# recco-rig.net
KiCad netlist of a schematic drawn in EAGLE
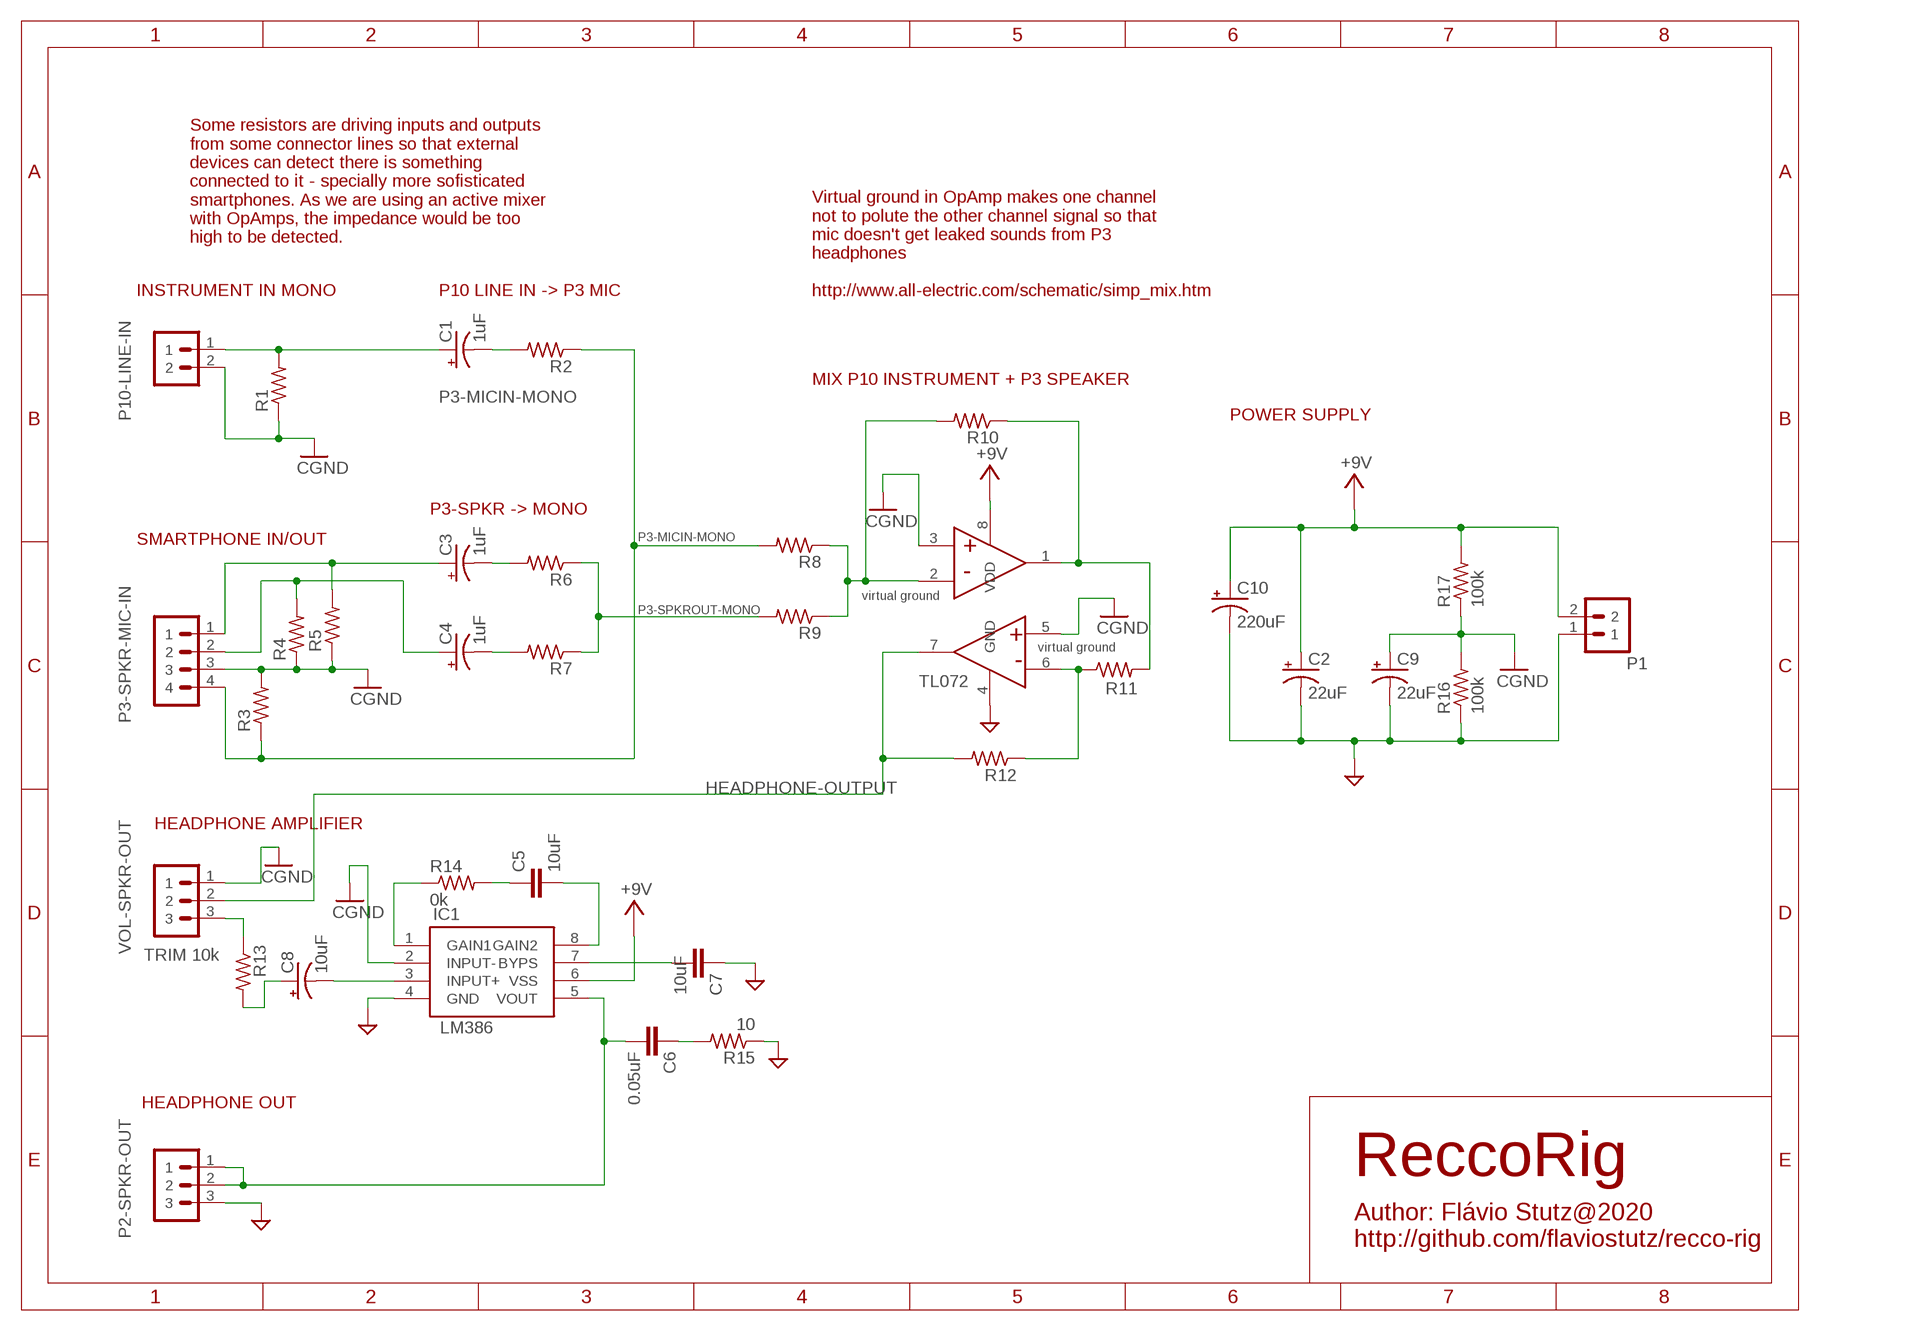
[diagram p0: schematic, sheet 1]

(export (version "E")
  (design (tool "Eeschema 10.0.6"))
  (components
    (comp (ref "C1")
      (value "1uF")
      (footprint "eagle-import:E2,5-6E")
      (libsource (lib "eagle-import") (part "CPOL-USE2,5-6E"))
    )
    (comp (ref "C2")
      (value "22uF")
      (footprint "eagle-import:E2,5-6E")
      (libsource (lib "eagle-import") (part "CPOL-USE2,5-6E"))
    )
    (comp (ref "C3")
      (value "1uF")
      (footprint "eagle-import:E2,5-6E")
      (libsource (lib "eagle-import") (part "CPOL-USE2,5-6E"))
    )
    (comp (ref "C4")
      (value "1uF")
      (footprint "eagle-import:E2,5-6E")
      (libsource (lib "eagle-import") (part "CPOL-USE2,5-6E"))
    )
    (comp (ref "C5")
      (value "10uF")
      (footprint "eagle-import:C050-024X044")
      (libsource (lib "eagle-import") (part "C-EU050-024X044"))
    )
    (comp (ref "C6")
      (value "0.05uF")
      (footprint "eagle-import:C050-024X044")
      (libsource (lib "eagle-import") (part "C-EU050-024X044"))
    )
    (comp (ref "C7")
      (value "10uF")
      (footprint "eagle-import:C050-024X044")
      (libsource (lib "eagle-import") (part "C-EU050-024X044"))
    )
    (comp (ref "C8")
      (value "10uF")
      (footprint "eagle-import:E2,5-6E")
      (libsource (lib "eagle-import") (part "CPOL-USE2,5-6E"))
    )
    (comp (ref "C9")
      (value "22uF")
      (footprint "eagle-import:E2,5-6E")
      (libsource (lib "eagle-import") (part "CPOL-USE2,5-6E"))
    )
    (comp (ref "C10")
      (value "220uF")
      (footprint "eagle-import:E2,5-6E")
      (libsource (lib "eagle-import") (part "CPOL-USE2,5-6E"))
    )
    (comp (ref "IC1")
      (value "LM386")
      (footprint "eagle-import:PDIP-8PIN")
      (libsource (lib "eagle-import") (part "LM386"))
    )
    (comp (ref "IC2")
      (value "TL072-OPAMP")
      (footprint "eagle-import:PDIP-8PIN")
      (fields (field (name "SPICEPREFIX") "X"))
      (libsource (lib "eagle-import") (part "TL072-OPAMP"))
    )
    (comp (ref "P1")
      (value "PIN-HEADER-2PIN")
      (footprint "eagle-import:PIN-HEADER-2PIN")
      (libsource (lib "eagle-import") (part "PIN-HEADER-2PIN"))
    )
    (comp (ref "P2-SPKR-OUT")
      (value "PIN-HEADER-3PIN")
      (footprint "eagle-import:PIN-HEADER-3PIN")
      (libsource (lib "eagle-import") (part "PIN-HEADER-3PIN"))
    )
    (comp (ref "P3-SPKR-MIC-IN")
      (value "PIN-HEADER-4PIN")
      (footprint "eagle-import:PIN-HEADER-4PIN")
      (libsource (lib "eagle-import") (part "PIN-HEADER-4PIN"))
    )
    (comp (ref "P10-LINE-IN")
      (value "PIN-HEADER-2PIN")
      (footprint "eagle-import:PIN-HEADER-2PIN")
      (libsource (lib "eagle-import") (part "PIN-HEADER-2PIN"))
    )
    (comp (ref "R1")
      (value "10k")
      (footprint "eagle-import:RESISTOR-V1")
      (libsource (lib "eagle-import") (part "RESISTORV1"))
    )
    (comp (ref "R2")
      (value "300ohm")
      (footprint "eagle-import:RESISTOR-V1")
      (libsource (lib "eagle-import") (part "RESISTORV1"))
    )
    (comp (ref "R3")
      (value "1k")
      (footprint "eagle-import:RESISTOR-V1")
      (libsource (lib "eagle-import") (part "RESISTORV1"))
    )
    (comp (ref "R4")
      (value "1k")
      (footprint "eagle-import:RESISTOR-V1")
      (fields (field (name "SPICEPREFIX") "R"))
      (libsource (lib "eagle-import") (part "RESISTORV1"))
    )
    (comp (ref "R5")
      (value "1k")
      (footprint "eagle-import:RESISTOR-V1")
      (libsource (lib "eagle-import") (part "RESISTORV1"))
    )
    (comp (ref "R6")
      (value "300ohm")
      (footprint "eagle-import:RESISTOR-V1")
      (libsource (lib "eagle-import") (part "RESISTORV1"))
    )
    (comp (ref "R7")
      (value "300ohm")
      (footprint "eagle-import:RESISTOR-V1")
      (libsource (lib "eagle-import") (part "RESISTORV1"))
    )
    (comp (ref "R8")
      (value "10k")
      (footprint "eagle-import:RESISTOR-V1")
      (libsource (lib "eagle-import") (part "RESISTORV1"))
    )
    (comp (ref "R9")
      (value "10k")
      (footprint "eagle-import:RESISTOR-V1")
      (libsource (lib "eagle-import") (part "RESISTORV1"))
    )
    (comp (ref "R10")
      (value "10k")
      (footprint "eagle-import:RESISTOR-V1")
      (libsource (lib "eagle-import") (part "RESISTORV1"))
    )
    (comp (ref "R11")
      (value "10k")
      (footprint "eagle-import:RESISTOR-V1")
      (libsource (lib "eagle-import") (part "RESISTORV1"))
    )
    (comp (ref "R12")
      (value "10k")
      (footprint "eagle-import:RESISTOR-V1")
      (libsource (lib "eagle-import") (part "RESISTORV1"))
    )
    (comp (ref "R13")
      (value "100ohm")
      (footprint "eagle-import:RESISTOR-V1")
      (libsource (lib "eagle-import") (part "RESISTORV1"))
    )
    (comp (ref "R14")
      (value "0k")
      (footprint "eagle-import:0309V")
      (libsource (lib "eagle-import") (part "R-US_0309/V"))
    )
    (comp (ref "R15")
      (value "10")
      (footprint "eagle-import:0309V")
      (libsource (lib "eagle-import") (part "R-US_0309/V"))
    )
    (comp (ref "R16")
      (value "100k")
      (footprint "eagle-import:0309V")
      (libsource (lib "eagle-import") (part "R-US_0309/V"))
    )
    (comp (ref "R17")
      (value "100k")
      (footprint "eagle-import:0309V")
      (libsource (lib "eagle-import") (part "R-US_0309/V"))
    )
    (comp (ref "VOL-SPKR-OUT")
      (value "HEADPHONE-VOLUME-KNOB")
      (footprint "eagle-import:PIN-HEADER-3PIN")
      (libsource (lib "eagle-import") (part "PIN-HEADER-3PIN"))
    )
  )
  (nets
    (net (code "1") (name "+9V") (class "Default")
      (node (ref "C10") (pin "+") (pinfunction "+_+") (pintype "passive"))
      (node (ref "C2") (pin "+") (pinfunction "+_+") (pintype "passive"))
      (node (ref "IC1") (pin "6") (pinfunction "VSS_6") (pintype "power_in"))
      (node (ref "IC2") (pin "8") (pinfunction "VDD_8") (pintype "power_in"))
      (node (ref "P1") (pin "2") (pinfunction "2_2") (pintype "passive"))
      (node (ref "R17") (pin "2") (pinfunction "2_2") (pintype "passive"))
    )
    (net (code "2") (name "/HEADPHONE-OUTPUT") (class "Default")
      (node (ref "IC2") (pin "7") (pinfunction "2OUT_7") (pintype "output"))
      (node (ref "R12") (pin "2") (pinfunction "2_2") (pintype "passive"))
      (node (ref "VOL-SPKR-OUT") (pin "2") (pinfunction "2_2") (pintype "passive"))
    )
    (net (code "3") (name "/P3-MICIN-MONO") (class "Default")
      (node (ref "P3-SPKR-MIC-IN") (pin "4") (pinfunction "4_4") (pintype "passive"))
      (node (ref "R2") (pin "1") (pinfunction "1_1") (pintype "passive"))
      (node (ref "R3") (pin "1") (pinfunction "1_1") (pintype "passive"))
      (node (ref "R8") (pin "2") (pinfunction "2_2") (pintype "passive"))
    )
    (net (code "4") (name "/P3-SPKROUT-MONO") (class "Default")
      (node (ref "R6") (pin "1") (pinfunction "1_1") (pintype "passive"))
      (node (ref "R7") (pin "1") (pinfunction "1_1") (pintype "passive"))
      (node (ref "R9") (pin "2") (pinfunction "2_2") (pintype "passive"))
    )
    (net (code "5") (name "CGND") (class "Default")
      (node (ref "C10") (pin "-") (pinfunction "-_-") (pintype "passive"))
      (node (ref "C2") (pin "-") (pinfunction "-_-") (pintype "passive"))
      (node (ref "C7") (pin "1") (pinfunction "1_1") (pintype "passive"))
      (node (ref "C9") (pin "+") (pinfunction "+_+") (pintype "passive"))
      (node (ref "C9") (pin "-") (pinfunction "-_-") (pintype "passive"))
      (node (ref "IC1") (pin "2") (pinfunction "INPUT-_2") (pintype "input"))
      (node (ref "IC1") (pin "4") (pinfunction "GND_4") (pintype "power_in"))
      (node (ref "IC2") (pin "3") (pinfunction "1IN+_3") (pintype "input"))
      (node (ref "IC2") (pin "4") (pinfunction "GND_4") (pintype "power_in"))
      (node (ref "IC2") (pin "5") (pinfunction "2IN+_5") (pintype "input"))
      (node (ref "P1") (pin "1") (pinfunction "1_1") (pintype "passive"))
      (node (ref "P10-LINE-IN") (pin "2") (pinfunction "2_2") (pintype "passive"))
      (node (ref "P2-SPKR-OUT") (pin "3") (pinfunction "3_3") (pintype "passive"))
      (node (ref "P3-SPKR-MIC-IN") (pin "3") (pinfunction "3_3") (pintype "passive"))
      (node (ref "R1") (pin "1") (pinfunction "1_1") (pintype "passive"))
      (node (ref "R15") (pin "1") (pinfunction "1_1") (pintype "passive"))
      (node (ref "R16") (pin "1") (pinfunction "1_1") (pintype "passive"))
      (node (ref "R16") (pin "2") (pinfunction "2_2") (pintype "passive"))
      (node (ref "R17") (pin "1") (pinfunction "1_1") (pintype "passive"))
      (node (ref "R3") (pin "2") (pinfunction "2_2") (pintype "passive"))
      (node (ref "R4") (pin "1") (pinfunction "1_1") (pintype "passive"))
      (node (ref "R5") (pin "1") (pinfunction "1_1") (pintype "passive"))
      (node (ref "VOL-SPKR-OUT") (pin "1") (pinfunction "1_1") (pintype "passive"))
    )
    (net (code "6") (name "Net-(C1-Pad+)") (class "Default")
      (node (ref "C1") (pin "+") (pinfunction "+_+") (pintype "passive"))
      (node (ref "P10-LINE-IN") (pin "1") (pinfunction "1_1") (pintype "passive"))
      (node (ref "R1") (pin "2") (pinfunction "2_2") (pintype "passive"))
    )
    (net (code "7") (name "Net-(C1-Pad-)") (class "Default")
      (node (ref "C1") (pin "-") (pinfunction "-_-") (pintype "passive"))
      (node (ref "R2") (pin "2") (pinfunction "2_2") (pintype "passive"))
    )
    (net (code "8") (name "Net-(C3-Pad+)") (class "Default")
      (node (ref "C3") (pin "+") (pinfunction "+_+") (pintype "passive"))
      (node (ref "P3-SPKR-MIC-IN") (pin "1") (pinfunction "1_1") (pintype "passive"))
      (node (ref "R5") (pin "2") (pinfunction "2_2") (pintype "passive"))
    )
    (net (code "9") (name "Net-(C3-Pad-)") (class "Default")
      (node (ref "C3") (pin "-") (pinfunction "-_-") (pintype "passive"))
      (node (ref "R6") (pin "2") (pinfunction "2_2") (pintype "passive"))
    )
    (net (code "10") (name "Net-(C4-Pad+)") (class "Default")
      (node (ref "C4") (pin "+") (pinfunction "+_+") (pintype "passive"))
      (node (ref "P3-SPKR-MIC-IN") (pin "2") (pinfunction "2_2") (pintype "passive"))
      (node (ref "R4") (pin "2") (pinfunction "2_2") (pintype "passive"))
    )
    (net (code "11") (name "Net-(C4-Pad-)") (class "Default")
      (node (ref "C4") (pin "-") (pinfunction "-_-") (pintype "passive"))
      (node (ref "R7") (pin "2") (pinfunction "2_2") (pintype "passive"))
    )
    (net (code "12") (name "Net-(C5-Pad1)") (class "Default")
      (node (ref "C5") (pin "1") (pinfunction "1_1") (pintype "passive"))
      (node (ref "R14") (pin "2") (pinfunction "2_2") (pintype "passive"))
    )
    (net (code "13") (name "Net-(C6-Pad1)") (class "Default")
      (node (ref "C6") (pin "1") (pinfunction "1_1") (pintype "passive"))
      (node (ref "R15") (pin "2") (pinfunction "2_2") (pintype "passive"))
    )
    (net (code "14") (name "Net-(C8-Pad+)") (class "Default")
      (node (ref "C8") (pin "+") (pinfunction "+_+") (pintype "passive"))
      (node (ref "R13") (pin "2") (pinfunction "2_2") (pintype "passive"))
    )
    (net (code "15") (name "Net-(IC1-BYPS)") (class "Default")
      (node (ref "C7") (pin "2") (pinfunction "2_2") (pintype "passive"))
      (node (ref "IC1") (pin "7") (pinfunction "BYPS_7") (pintype "output"))
    )
    (net (code "16") (name "Net-(IC1-GAIN1)") (class "Default")
      (node (ref "IC1") (pin "1") (pinfunction "GAIN1_1") (pintype "passive"))
      (node (ref "R14") (pin "1") (pinfunction "1_1") (pintype "passive"))
    )
    (net (code "17") (name "Net-(IC1-GAIN2)") (class "Default")
      (node (ref "C5") (pin "2") (pinfunction "2_2") (pintype "passive"))
      (node (ref "IC1") (pin "8") (pinfunction "GAIN2_8") (pintype "passive"))
    )
    (net (code "18") (name "Net-(IC1-INPUT+)") (class "Default")
      (node (ref "C8") (pin "-") (pinfunction "-_-") (pintype "passive"))
      (node (ref "IC1") (pin "3") (pinfunction "INPUT+_3") (pintype "input"))
    )
    (net (code "19") (name "Net-(IC1-VOUT)") (class "Default")
      (node (ref "C6") (pin "2") (pinfunction "2_2") (pintype "passive"))
      (node (ref "IC1") (pin "5") (pinfunction "VOUT_5") (pintype "output"))
      (node (ref "P2-SPKR-OUT") (pin "1") (pinfunction "1_1") (pintype "passive"))
      (node (ref "P2-SPKR-OUT") (pin "2") (pinfunction "2_2") (pintype "passive"))
    )
    (net (code "20") (name "Net-(IC2-1IN-)") (class "Default")
      (node (ref "IC2") (pin "2") (pinfunction "1IN-_2") (pintype "input"))
      (node (ref "R10") (pin "2") (pinfunction "2_2") (pintype "passive"))
      (node (ref "R8") (pin "1") (pinfunction "1_1") (pintype "passive"))
      (node (ref "R9") (pin "1") (pinfunction "1_1") (pintype "passive"))
    )
    (net (code "21") (name "Net-(IC2-1OUT)") (class "Default")
      (node (ref "IC2") (pin "1") (pinfunction "1OUT_1") (pintype "output"))
      (node (ref "R10") (pin "1") (pinfunction "1_1") (pintype "passive"))
      (node (ref "R11") (pin "2") (pinfunction "2_2") (pintype "passive"))
    )
    (net (code "22") (name "Net-(IC2-2IN-)") (class "Default")
      (node (ref "IC2") (pin "6") (pinfunction "2IN-_6") (pintype "input"))
      (node (ref "R11") (pin "1") (pinfunction "1_1") (pintype "passive"))
      (node (ref "R12") (pin "1") (pinfunction "1_1") (pintype "passive"))
    )
    (net (code "23") (name "Net-(R13-Pad1)") (class "Default")
      (node (ref "R13") (pin "1") (pinfunction "1_1") (pintype "passive"))
      (node (ref "VOL-SPKR-OUT") (pin "3") (pinfunction "3_3") (pintype "passive"))
    )
  )
)
